# M.net
KiCad netlist of a schematic drawn in Altium Designer
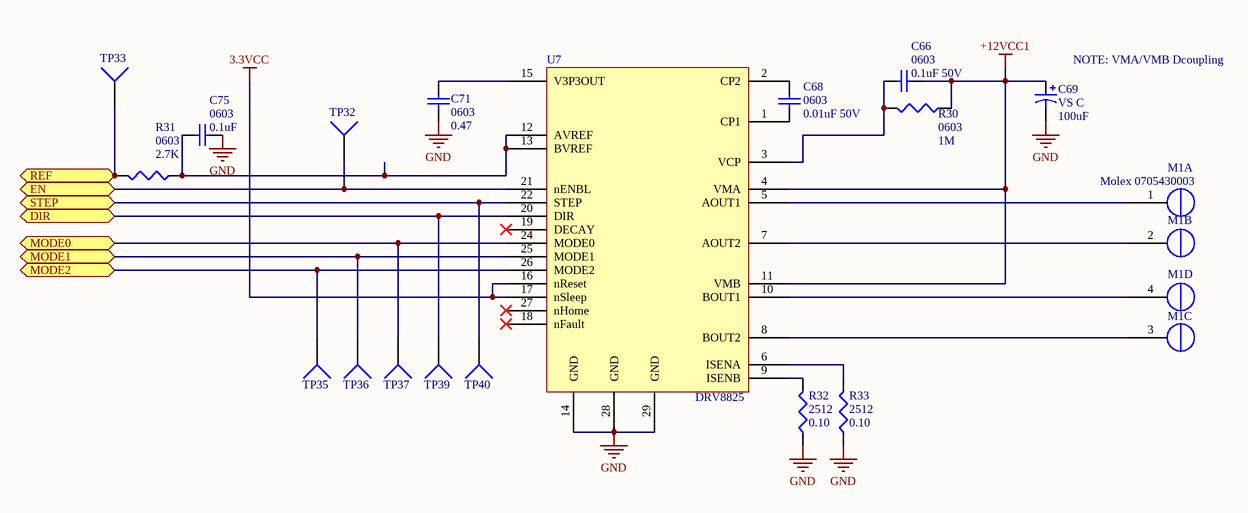
[diagram p0: M.SchDoc]

(export (version "E")
  (design (tool "Eeschema 10.0.6"))
  (components
    (comp (ref "C66")
      (value "0603")
      (footprint "1608[0603]")
      (description "Capacitor (Semiconductor SIM Model)")
      (fields (field (name "ALTIUM_VALUE") "0.1uF 50V") (field (name "PUBLISHER") "Altium Limited"))
      (libsource (lib "Miscellaneous Devices") (part "Cap Semi"))
    )
    (comp (ref "C68")
      (value "0603")
      (footprint "1608[0603]")
      (description "Capacitor (Semiconductor SIM Model)")
      (fields (field (name "ALTIUM_VALUE") "0.01uF 50V") (field (name "PUBLISHER") "Altium Limited"))
      (libsource (lib "Miscellaneous Devices") (part "Cap Semi"))
    )
    (comp (ref "C69")
      (value "VS C")
      (footprint "Panasonic VS C")
      (description "Polarized Capacitor (Radial)")
      (fields (field (name "ALTIUM_VALUE") "100uF") (field (name "PUBLISHER") "Altium Limited"))
      (libsource (lib "Miscellaneous Devices") (part "Cap Pol1"))
    )
    (comp (ref "C71")
      (value "0603")
      (footprint "1608[0603]")
      (description "Capacitor (Semiconductor SIM Model)")
      (fields (field (name "ALTIUM_VALUE") "0.47") (field (name "PUBLISHER") "Altium Limited"))
      (libsource (lib "Miscellaneous Devices") (part "Cap Semi"))
    )
    (comp (ref "C75")
      (value "0603")
      (footprint "1608[0603]")
      (description "Capacitor (Semiconductor SIM Model)")
      (fields (field (name "ALTIUM_VALUE") "0.1uF") (field (name "PUBLISHER") "Altium Limited"))
      (libsource (lib "Miscellaneous Devices") (part "Cap Semi"))
    )
    (comp (ref "M1")
      (value "Molex 0705430003")
      (footprint "4POL254")
      (description "Molex 4 Pin Clip Connector")
      (libsource (lib "ZMBo Schematic Library") (part "Molex 0705430003 Alt"))
    )
    (comp (ref "R30")
      (value "0603")
      (footprint "J1-0603")
      (description "Resistor")
      (fields (field (name "ALTIUM_VALUE") "1M") (field (name "PUBLISHER") "Altium Limited"))
      (libsource (lib "Miscellaneous Devices") (part "Res3"))
    )
    (comp (ref "R31")
      (value "0603")
      (footprint "J1-0603")
      (description "Resistor")
      (fields (field (name "ALTIUM_VALUE") "2.7K") (field (name "PUBLISHER") "Altium Limited"))
      (libsource (lib "Miscellaneous Devices") (part "Res3"))
    )
    (comp (ref "R32")
      (value "2512")
      (footprint "Resistor2512")
      (description "Resistor")
      (fields (field (name "ALTIUM_VALUE") "0.10") (field (name "PUBLISHER") "Altium Limited"))
      (libsource (lib "Miscellaneous Devices") (part "Res3"))
    )
    (comp (ref "R33")
      (value "2512")
      (footprint "Resistor2512")
      (description "Resistor")
      (fields (field (name "ALTIUM_VALUE") "0.10") (field (name "PUBLISHER") "Altium Limited"))
      (libsource (lib "Miscellaneous Devices") (part "Res3"))
    )
    (comp (ref "TP32")
      (value "TP4")
      (footprint "TP-2")
      (description "Socket")
      (fields (field (name "PUBLISHER") "Altium Limited"))
      (libsource (lib "ZMBo Schematic Library") (part "Socket"))
    )
    (comp (ref "TP33")
      (value "TP4")
      (footprint "TP-2")
      (description "Socket")
      (fields (field (name "PUBLISHER") "Altium Limited"))
      (libsource (lib "ZMBo Schematic Library") (part "Socket"))
    )
    (comp (ref "TP35")
      (value "TP4")
      (footprint "TP-2")
      (description "Socket")
      (fields (field (name "PUBLISHER") "Altium Limited"))
      (libsource (lib "ZMBo Schematic Library") (part "Socket"))
    )
    (comp (ref "TP36")
      (value "TP4")
      (footprint "TP-2")
      (description "Socket")
      (fields (field (name "PUBLISHER") "Altium Limited"))
      (libsource (lib "ZMBo Schematic Library") (part "Socket"))
    )
    (comp (ref "TP37")
      (value "TP4")
      (footprint "TP-2")
      (description "Socket")
      (fields (field (name "PUBLISHER") "Altium Limited"))
      (libsource (lib "ZMBo Schematic Library") (part "Socket"))
    )
    (comp (ref "TP39")
      (value "TP4")
      (footprint "TP-2")
      (description "Socket")
      (fields (field (name "PUBLISHER") "Altium Limited"))
      (libsource (lib "ZMBo Schematic Library") (part "Socket"))
    )
    (comp (ref "TP40")
      (value "TP4")
      (footprint "TP-2")
      (description "Socket")
      (fields (field (name "PUBLISHER") "Altium Limited"))
      (libsource (lib "ZMBo Schematic Library") (part "Socket"))
    )
    (comp (ref "U7")
      (value "DRV8825")
      (footprint "DRV8825")
      (description "DRV8825 Ti Stepper Driver")
      (libsource (lib "ZMBo Schematic Library") (part "DRV8825"))
    )
  )
  (nets
    (net (code "1") (name "+12VCC1") (class "Default")
      (node (ref "C66") (pin "1") (pinfunction "1_1") (pintype "passive"))
      (node (ref "C69") (pin "1") (pinfunction "1_1") (pintype "passive"))
      (node (ref "R30") (pin "1") (pinfunction "1_1") (pintype "passive"))
      (node (ref "U7") (pin "11") (pinfunction "VMB_11") (pintype "passive"))
      (node (ref "U7") (pin "4") (pinfunction "VMA_4") (pintype "passive"))
    )
    (net (code "2") (name "/DIR") (class "Default")
      (node (ref "TP39") (pin "1") (pinfunction "1_1") (pintype "passive"))
      (node (ref "U7") (pin "20") (pinfunction "DIR_20") (pintype "passive"))
    )
    (net (code "3") (name "/EN") (class "Default")
      (node (ref "TP32") (pin "1") (pinfunction "1_1") (pintype "passive"))
      (node (ref "U7") (pin "21") (pinfunction "nENBL_21") (pintype "passive"))
    )
    (net (code "4") (name "/MODE0") (class "Default")
      (node (ref "TP37") (pin "1") (pinfunction "1_1") (pintype "passive"))
      (node (ref "U7") (pin "24") (pinfunction "MODE0_24") (pintype "passive"))
    )
    (net (code "5") (name "/MODE1") (class "Default")
      (node (ref "TP36") (pin "1") (pinfunction "1_1") (pintype "passive"))
      (node (ref "U7") (pin "25") (pinfunction "MODE1_25") (pintype "passive"))
    )
    (net (code "6") (name "/MODE2") (class "Default")
      (node (ref "TP35") (pin "1") (pinfunction "1_1") (pintype "passive"))
      (node (ref "U7") (pin "26") (pinfunction "MODE2_26") (pintype "passive"))
    )
    (net (code "7") (name "/REF") (class "Default")
      (node (ref "R31") (pin "2") (pinfunction "2_2") (pintype "passive"))
      (node (ref "TP33") (pin "1") (pinfunction "1_1") (pintype "passive"))
    )
    (net (code "8") (name "/STEP") (class "Default")
      (node (ref "TP40") (pin "1") (pinfunction "1_1") (pintype "passive"))
      (node (ref "U7") (pin "22") (pinfunction "STEP_22") (pintype "passive"))
    )
    (net (code "9") (name "3.3VCC") (class "Default")
      (node (ref "U7") (pin "16") (pinfunction "nReset_16") (pintype "passive"))
      (node (ref "U7") (pin "17") (pinfunction "nSleep_17") (pintype "passive"))
    )
    (net (code "10") (name "GND") (class "Default")
      (node (ref "C69") (pin "2") (pinfunction "2_2") (pintype "passive"))
      (node (ref "C71") (pin "1") (pinfunction "1_1") (pintype "passive"))
      (node (ref "C75") (pin "1") (pinfunction "1_1") (pintype "passive"))
      (node (ref "R32") (pin "1") (pinfunction "1_1") (pintype "passive"))
      (node (ref "R33") (pin "1") (pinfunction "1_1") (pintype "passive"))
      (node (ref "U7") (pin "14") (pinfunction "GND_14") (pintype "passive"))
      (node (ref "U7") (pin "28") (pinfunction "GND_28") (pintype "passive"))
      (node (ref "U7") (pin "29") (pinfunction "GND_29") (pintype "passive"))
    )
    (net (code "11") (name "Net-(M1A-OUT2B)") (class "Default")
      (node (ref "M1") (pin "1") (pinfunction "OUT2B_1") (pintype "passive"))
      (node (ref "U7") (pin "5") (pinfunction "AOUT1_5") (pintype "passive"))
    )
    (net (code "12") (name "Net-(M1B-OUT2A)") (class "Default")
      (node (ref "M1") (pin "2") (pinfunction "OUT2A_2") (pintype "passive"))
      (node (ref "U7") (pin "7") (pinfunction "AOUT2_7") (pintype "passive"))
    )
    (net (code "13") (name "Net-(M1C-OUT1A)") (class "Default")
      (node (ref "M1") (pin "3") (pinfunction "OUT1A_3") (pintype "passive"))
      (node (ref "U7") (pin "8") (pinfunction "BOUT2_8") (pintype "passive"))
    )
    (net (code "14") (name "Net-(M1D-OUT1B)") (class "Default")
      (node (ref "M1") (pin "4") (pinfunction "OUT1B_4") (pintype "passive"))
      (node (ref "U7") (pin "10") (pinfunction "BOUT1_10") (pintype "passive"))
    )
    (net (code "15") (name "Net-(U7-AVREF)") (class "Default")
      (node (ref "C75") (pin "2") (pinfunction "2_2") (pintype "passive"))
      (node (ref "R31") (pin "1") (pinfunction "1_1") (pintype "passive"))
      (node (ref "U7") (pin "12") (pinfunction "AVREF_12") (pintype "passive"))
      (node (ref "U7") (pin "13") (pinfunction "BVREF_13") (pintype "passive"))
    )
    (net (code "16") (name "Net-(U7-CP1)") (class "Default")
      (node (ref "C68") (pin "1") (pinfunction "1_1") (pintype "passive"))
      (node (ref "U7") (pin "1") (pinfunction "CP1_1") (pintype "passive"))
    )
    (net (code "17") (name "Net-(U7-CP2)") (class "Default")
      (node (ref "C68") (pin "2") (pinfunction "2_2") (pintype "passive"))
      (node (ref "U7") (pin "2") (pinfunction "CP2_2") (pintype "passive"))
    )
    (net (code "18") (name "Net-(U7-ISENA)") (class "Default")
      (node (ref "R33") (pin "2") (pinfunction "2_2") (pintype "passive"))
      (node (ref "U7") (pin "6") (pinfunction "ISENA_6") (pintype "passive"))
    )
    (net (code "19") (name "Net-(U7-ISENB)") (class "Default")
      (node (ref "R32") (pin "2") (pinfunction "2_2") (pintype "passive"))
      (node (ref "U7") (pin "9") (pinfunction "ISENB_9") (pintype "passive"))
    )
    (net (code "20") (name "Net-(U7-V3P3OUT)") (class "Default")
      (node (ref "C71") (pin "2") (pinfunction "2_2") (pintype "passive"))
      (node (ref "U7") (pin "15") (pinfunction "V3P3OUT_15") (pintype "passive"))
    )
    (net (code "21") (name "Net-(U7-VCP)") (class "Default")
      (node (ref "C66") (pin "2") (pinfunction "2_2") (pintype "passive"))
      (node (ref "R30") (pin "2") (pinfunction "2_2") (pintype "passive"))
      (node (ref "U7") (pin "3") (pinfunction "VCP_3") (pintype "passive"))
    )
    (net (code "22") (name "unconnected-(U7-DECAY-Pad19)") (class "Default")
      (node (ref "U7") (pin "19") (pinfunction "DECAY_19") (pintype "passive+no_connect"))
    )
    (net (code "23") (name "unconnected-(U7-NC-Pad23)") (class "Default")
      (node (ref "U7") (pin "23") (pinfunction "NC_23") (pintype "passive"))
    )
    (net (code "24") (name "unconnected-(U7-nFault-Pad18)") (class "Default")
      (node (ref "U7") (pin "18") (pinfunction "nFault_18") (pintype "passive+no_connect"))
    )
    (net (code "25") (name "unconnected-(U7-nHome-Pad27)") (class "Default")
      (node (ref "U7") (pin "27") (pinfunction "nHome_27") (pintype "passive+no_connect"))
    )
  )
)
